# board_0_7v.net
KiCad netlist of a schematic drawn in EAGLE
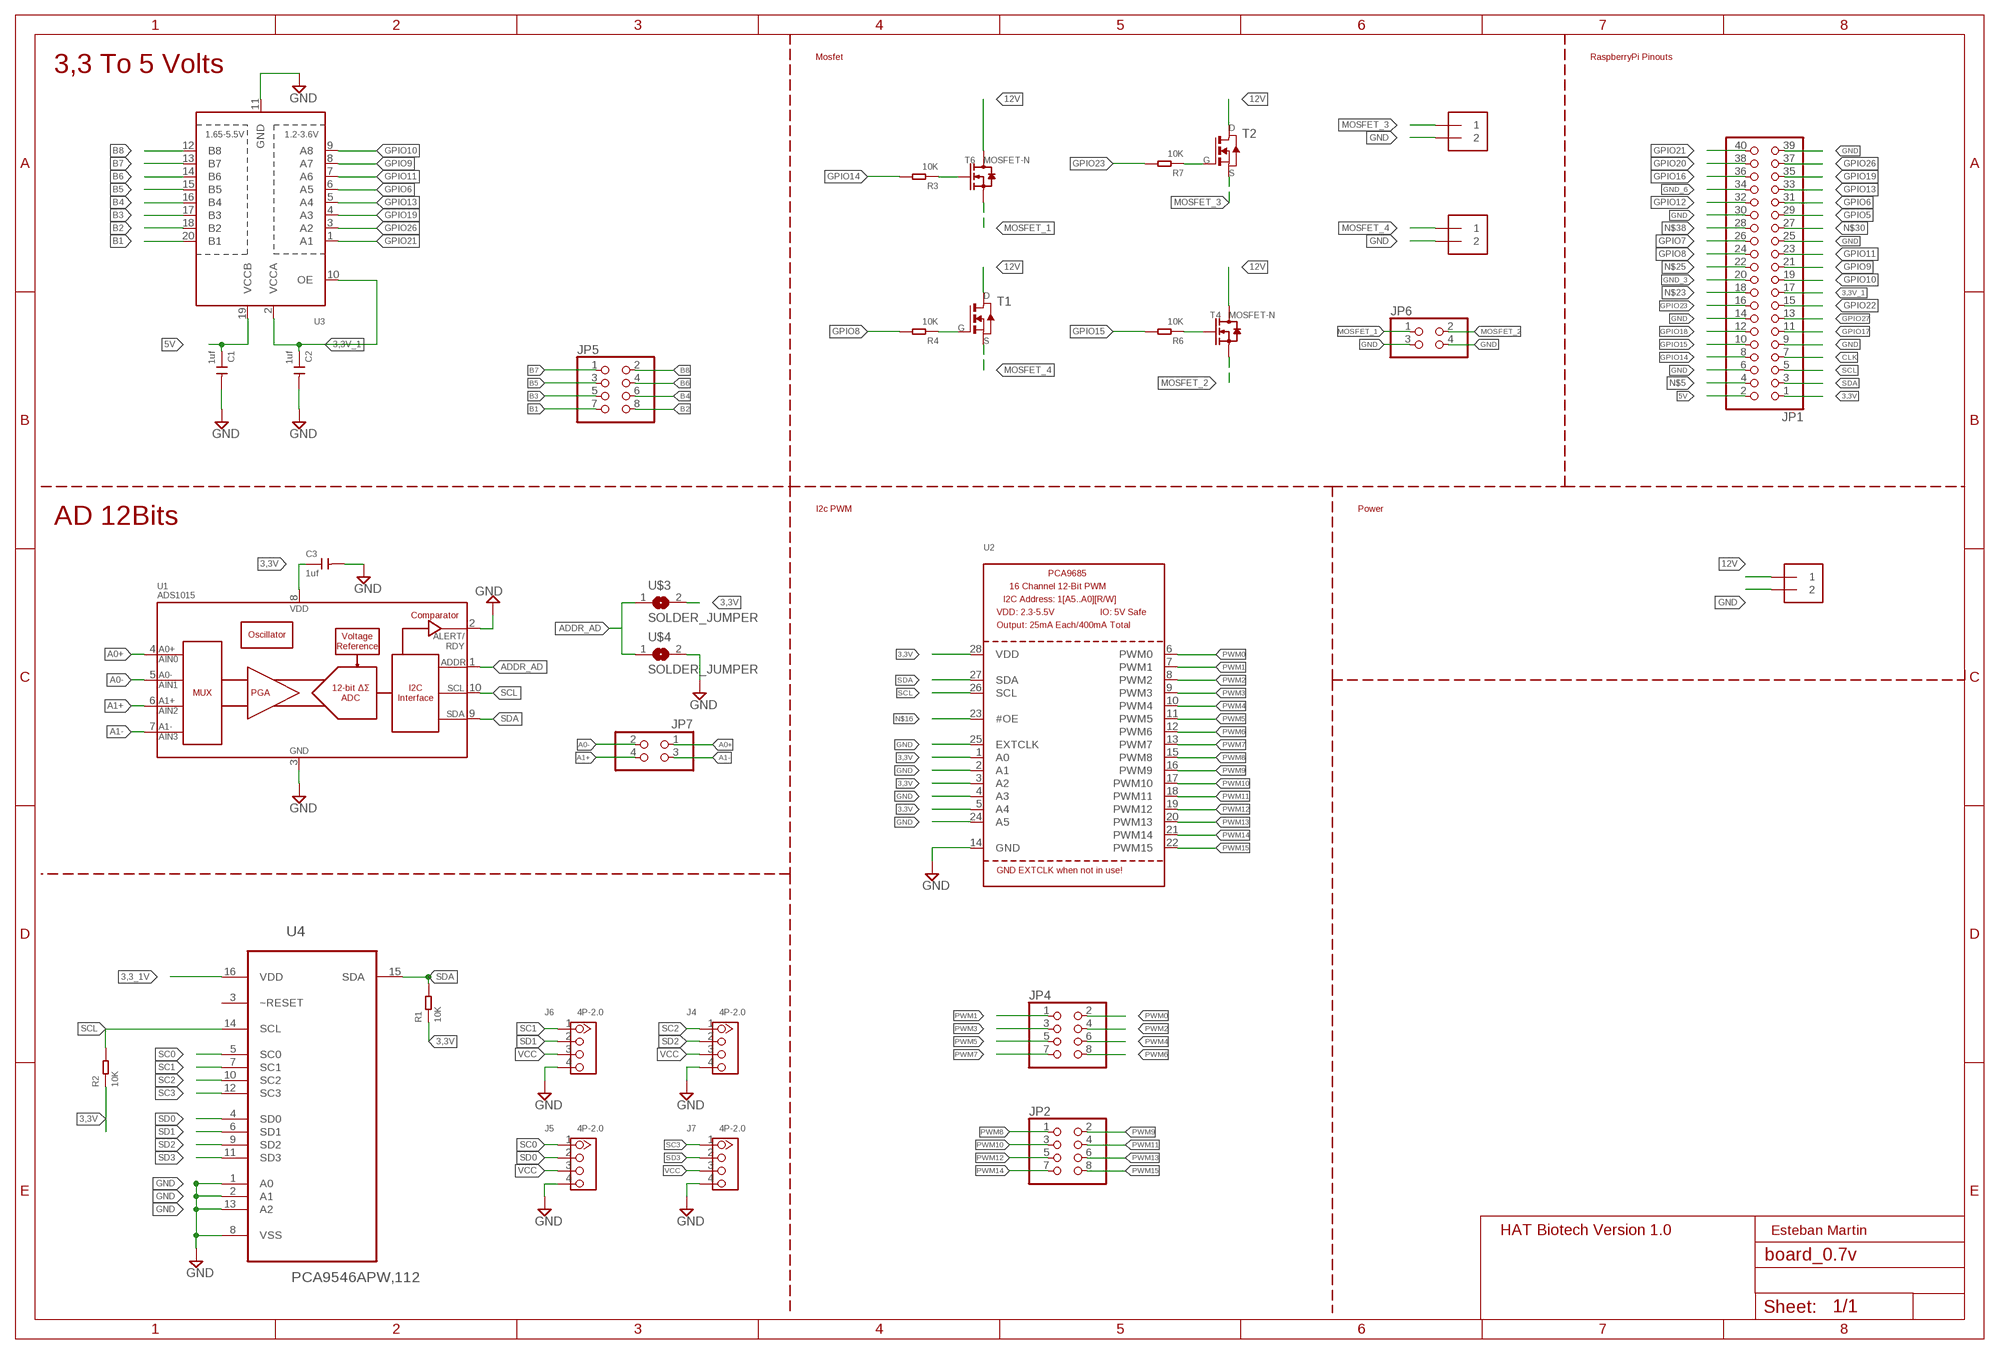
[diagram p0: schematic, sheet 1]

(export (version "E")
  (design (tool "Eeschema 10.0.6"))
  (components
    (comp (ref "C1")
      (value "1uf")
      (footprint "eagle-import:C0805")
      (fields (field (name "MPN") "CC0805KKX7R8BB105"))
      (libsource (lib "eagle-import") (part "CERAMIC-1UF-25V-10%-X7R(0805)"))
    )
    (comp (ref "C2")
      (value "1uf")
      (footprint "eagle-import:C0805")
      (fields (field (name "MPN") "CC0805KKX7R8BB105"))
      (libsource (lib "eagle-import") (part "CERAMIC-1UF-25V-10%-X7R(0805)"))
    )
    (comp (ref "C3")
      (value "1uf")
      (footprint "eagle-import:C0805")
      (fields (field (name "MPN") "CC0805KKX7R8BB105"))
      (libsource (lib "eagle-import") (part "CERAMIC-1UF-25V-10%-X7R(0805)"))
    )
    (comp (ref "J1")
      (value "1X2-3.5MM")
      (footprint "eagle-import:1X2-3.5MM")
      (libsource (lib "eagle-import") (part "1X2-3.5MM"))
    )
    (comp (ref "J2")
      (value "1X2-3.5MM")
      (footprint "eagle-import:1X2-3.5MM")
      (libsource (lib "eagle-import") (part "1X2-3.5MM"))
    )
    (comp (ref "J3")
      (value "1X2-3.5MM")
      (footprint "eagle-import:1X2-3.5MM")
      (libsource (lib "eagle-import") (part "1X2-3.5MM"))
    )
    (comp (ref "J4")
      (value "4P-2.0")
      (footprint "eagle-import:HW4-2.0")
      (libsource (lib "eagle-import") (part "GROVE-CONNECTOR-DIP(4P-2.0)"))
    )
    (comp (ref "J5")
      (value "4P-2.0")
      (footprint "eagle-import:HW4-2.0")
      (libsource (lib "eagle-import") (part "GROVE-CONNECTOR-DIP(4P-2.0)"))
    )
    (comp (ref "J6")
      (value "4P-2.0")
      (footprint "eagle-import:HW4-2.0")
      (libsource (lib "eagle-import") (part "GROVE-CONNECTOR-DIP(4P-2.0)"))
    )
    (comp (ref "J7")
      (value "4P-2.0")
      (footprint "eagle-import:HW4-2.0")
      (libsource (lib "eagle-import") (part "GROVE-CONNECTOR-DIP(4P-2.0)"))
    )
    (comp (ref "JP1")
      (value "PINHD-2X20")
      (footprint "eagle-import:2X20")
      (libsource (lib "eagle-import") (part "PINHD-2X20"))
    )
    (comp (ref "JP2")
      (value "PINHD-2X4")
      (footprint "eagle-import:2X04")
      (libsource (lib "eagle-import") (part "PINHD-2X4"))
    )
    (comp (ref "JP4")
      (value "PINHD-2X4")
      (footprint "eagle-import:2X04")
      (libsource (lib "eagle-import") (part "PINHD-2X4"))
    )
    (comp (ref "JP5")
      (value "PINHD-2X4")
      (footprint "eagle-import:2X04")
      (libsource (lib "eagle-import") (part "PINHD-2X4"))
    )
    (comp (ref "JP6")
      (value "PINHD-2X2")
      (footprint "eagle-import:2X02")
      (libsource (lib "eagle-import") (part "PINHD-2X2"))
    )
    (comp (ref "JP7")
      (value "PINHD-2X2")
      (footprint "eagle-import:2X02")
      (libsource (lib "eagle-import") (part "PINHD-2X2"))
    )
    (comp (ref "R1")
      (value "10K")
      (footprint "eagle-import:R0805")
      (fields (field (name "MPN") "RC0805FR-0710KL"))
      (libsource (lib "eagle-import") (part "SMD-RES-10K-1%-1/8W(0805)"))
    )
    (comp (ref "R2")
      (value "10K")
      (footprint "eagle-import:R0805")
      (fields (field (name "MPN") "RC0805FR-0710KL"))
      (libsource (lib "eagle-import") (part "SMD-RES-10K-1%-1/8W(0805)"))
    )
    (comp (ref "R3")
      (value "10K")
      (footprint "eagle-import:R0805")
      (fields (field (name "MPN") "RC0805FR-0710KL"))
      (libsource (lib "eagle-import") (part "SMD-RES-10K-1%-1/8W(0805)"))
    )
    (comp (ref "R4")
      (value "10K")
      (footprint "eagle-import:R0805")
      (fields (field (name "MPN") "RC0805FR-0710KL"))
      (libsource (lib "eagle-import") (part "SMD-RES-10K-1%-1/8W(0805)"))
    )
    (comp (ref "R6")
      (value "10K")
      (footprint "eagle-import:R0805")
      (fields (field (name "MPN") "RC0805FR-0710KL"))
      (libsource (lib "eagle-import") (part "SMD-RES-10K-1%-1/8W(0805)"))
    )
    (comp (ref "R7")
      (value "10K")
      (footprint "eagle-import:R0805")
      (fields (field (name "MPN") "RC0805FR-0710KL"))
      (libsource (lib "eagle-import") (part "SMD-RES-10K-1%-1/8W(0805)"))
    )
    (comp (ref "T1")
      (value "NMOSFETTO252")
      (footprint "eagle-import:TO252")
      (libsource (lib "eagle-import") (part "NMOSFETTO252"))
    )
    (comp (ref "T2")
      (value "NMOSFETTO252")
      (footprint "eagle-import:TO252")
      (libsource (lib "eagle-import") (part "NMOSFETTO252"))
    )
    (comp (ref "T4")
      (value "MOSFET-N")
      (footprint "eagle-import:SOT-23")
      (libsource (lib "eagle-import") (part "MOSFET-N"))
    )
    (comp (ref "T6")
      (value "MOSFET-N")
      (footprint "eagle-import:SOT-23")
      (libsource (lib "eagle-import") (part "MOSFET-N"))
    )
    (comp (ref "U$3")
      (value "SOLDER_JUMPER")
      (footprint "eagle-import:SJFAB")
      (libsource (lib "eagle-import") (part "SOLDER_JUMPER"))
    )
    (comp (ref "U$4")
      (value "SOLDER_JUMPER")
      (footprint "eagle-import:SJFAB")
      (libsource (lib "eagle-import") (part "SOLDER_JUMPER"))
    )
    (comp (ref "U1")
      (value "ADS1015")
      (footprint "eagle-import:MSOP10")
      (libsource (lib "eagle-import") (part "ADS1015"))
    )
    (comp (ref "U2")
      (value "PCA9685")
      (footprint "eagle-import:TSSOP28")
      (libsource (lib "eagle-import") (part "PCA9685"))
    )
    (comp (ref "U3")
      (value "TXB0108PWR")
      (footprint "eagle-import:TSSOP20")
      (libsource (lib "eagle-import") (part "TXB0108PWR"))
    )
    (comp (ref "U4")
      (value "PCA9546APW,112")
      (footprint "eagle-import:SOP65P640X110-16N")
      (libsource (lib "eagle-import") (part "PCA9546APW,112"))
    )
  )
  (nets
    (net (code "1") (name "3,3V") (class "Default")
      (node (ref "C3") (pin "1") (pinfunction "1_1") (pintype "passive"))
      (node (ref "JP1") (pin "1") (pinfunction "1_1") (pintype "passive"))
      (node (ref "R1") (pin "1") (pinfunction "1_1") (pintype "passive"))
      (node (ref "R2") (pin "1") (pinfunction "1_1") (pintype "passive"))
      (node (ref "U$3") (pin "2") (pinfunction "2_2") (pintype "passive"))
      (node (ref "U1") (pin "8") (pinfunction "VDD_8") (pintype "bidirectional"))
      (node (ref "U2") (pin "1") (pinfunction "A0_1") (pintype "bidirectional"))
      (node (ref "U2") (pin "28") (pinfunction "VDD_28") (pintype "power_in"))
      (node (ref "U2") (pin "3") (pinfunction "A2_3") (pintype "bidirectional"))
      (node (ref "U2") (pin "5") (pinfunction "A4_5") (pintype "bidirectional"))
    )
    (net (code "2") (name "3,3V_1") (class "Default")
      (node (ref "C2") (pin "1") (pinfunction "1_1") (pintype "passive"))
      (node (ref "JP1") (pin "17") (pinfunction "17_17") (pintype "passive"))
      (node (ref "U3") (pin "10") (pinfunction "OE_10") (pintype "bidirectional"))
      (node (ref "U3") (pin "2") (pinfunction "VCCA_2") (pintype "bidirectional"))
    )
    (net (code "3") (name "3,3_1V") (class "Default")
      (node (ref "U4") (pin "16") (pinfunction "VDD_16") (pintype "power_in"))
    )
    (net (code "4") (name "5V") (class "Default")
      (node (ref "C1") (pin "1") (pinfunction "1_1") (pintype "passive"))
      (node (ref "JP1") (pin "2") (pinfunction "2_2") (pintype "passive"))
      (node (ref "U3") (pin "19") (pinfunction "VCCB_19") (pintype "bidirectional"))
    )
    (net (code "5") (name "12V") (class "Default")
      (node (ref "J2") (pin "1") (pinfunction "1_1") (pintype "passive"))
      (node (ref "T1") (pin "3") (pinfunction "D_3") (pintype "passive"))
      (node (ref "T2") (pin "3") (pinfunction "D_3") (pintype "passive"))
      (node (ref "T4") (pin "3") (pinfunction "D_3") (pintype "passive"))
      (node (ref "T6") (pin "3") (pinfunction "D_3") (pintype "passive"))
    )
    (net (code "6") (name "A0+") (class "Default")
      (node (ref "JP7") (pin "1") (pinfunction "1_1") (pintype "passive"))
      (node (ref "U1") (pin "4") (pinfunction "AIN0_4") (pintype "bidirectional"))
    )
    (net (code "7") (name "A0-") (class "Default")
      (node (ref "JP7") (pin "2") (pinfunction "2_2") (pintype "passive"))
      (node (ref "U1") (pin "5") (pinfunction "AIN1_5") (pintype "bidirectional"))
    )
    (net (code "8") (name "A1+") (class "Default")
      (node (ref "JP7") (pin "4") (pinfunction "4_4") (pintype "passive"))
      (node (ref "U1") (pin "6") (pinfunction "AIN2_6") (pintype "bidirectional"))
    )
    (net (code "9") (name "A1-") (class "Default")
      (node (ref "JP7") (pin "3") (pinfunction "3_3") (pintype "passive"))
      (node (ref "U1") (pin "7") (pinfunction "AIN3_7") (pintype "bidirectional"))
    )
    (net (code "10") (name "ADDR_AD") (class "Default")
      (node (ref "U$3") (pin "1") (pinfunction "1_1") (pintype "passive"))
      (node (ref "U$4") (pin "1") (pinfunction "1_1") (pintype "passive"))
      (node (ref "U1") (pin "1") (pinfunction "ADDR_1") (pintype "bidirectional"))
    )
    (net (code "11") (name "B1") (class "Default")
      (node (ref "JP5") (pin "7") (pinfunction "7_7") (pintype "passive"))
      (node (ref "U3") (pin "20") (pinfunction "B1_20") (pintype "bidirectional"))
    )
    (net (code "12") (name "B2") (class "Default")
      (node (ref "JP5") (pin "8") (pinfunction "8_8") (pintype "passive"))
      (node (ref "U3") (pin "18") (pinfunction "B2_18") (pintype "bidirectional"))
    )
    (net (code "13") (name "B3") (class "Default")
      (node (ref "JP5") (pin "5") (pinfunction "5_5") (pintype "passive"))
      (node (ref "U3") (pin "17") (pinfunction "B3_17") (pintype "bidirectional"))
    )
    (net (code "14") (name "B4") (class "Default")
      (node (ref "JP5") (pin "6") (pinfunction "6_6") (pintype "passive"))
      (node (ref "U3") (pin "16") (pinfunction "B4_16") (pintype "bidirectional"))
    )
    (net (code "15") (name "B5") (class "Default")
      (node (ref "JP5") (pin "3") (pinfunction "3_3") (pintype "passive"))
      (node (ref "U3") (pin "15") (pinfunction "B5_15") (pintype "bidirectional"))
    )
    (net (code "16") (name "B6") (class "Default")
      (node (ref "JP5") (pin "4") (pinfunction "4_4") (pintype "passive"))
      (node (ref "U3") (pin "14") (pinfunction "B6_14") (pintype "bidirectional"))
    )
    (net (code "17") (name "B7") (class "Default")
      (node (ref "JP5") (pin "1") (pinfunction "1_1") (pintype "passive"))
      (node (ref "U3") (pin "13") (pinfunction "B7_13") (pintype "bidirectional"))
    )
    (net (code "18") (name "B8") (class "Default")
      (node (ref "JP5") (pin "2") (pinfunction "2_2") (pintype "passive"))
      (node (ref "U3") (pin "12") (pinfunction "B8_12") (pintype "bidirectional"))
    )
    (net (code "19") (name "CLK") (class "Default")
      (node (ref "JP1") (pin "7") (pinfunction "7_7") (pintype "passive"))
    )
    (net (code "20") (name "GND") (class "Default")
      (node (ref "C1") (pin "2") (pinfunction "2_2") (pintype "passive"))
      (node (ref "C2") (pin "2") (pinfunction "2_2") (pintype "passive"))
      (node (ref "C3") (pin "2") (pinfunction "2_2") (pintype "passive"))
      (node (ref "J1") (pin "2") (pinfunction "2_2") (pintype "passive"))
      (node (ref "J2") (pin "2") (pinfunction "2_2") (pintype "passive"))
      (node (ref "J3") (pin "2") (pinfunction "2_2") (pintype "passive"))
      (node (ref "J4") (pin "4") (pinfunction "4_4") (pintype "bidirectional"))
      (node (ref "J5") (pin "4") (pinfunction "4_4") (pintype "bidirectional"))
      (node (ref "J6") (pin "4") (pinfunction "4_4") (pintype "bidirectional"))
      (node (ref "J7") (pin "4") (pinfunction "4_4") (pintype "bidirectional"))
      (node (ref "JP1") (pin "14") (pinfunction "14_14") (pintype "passive"))
      (node (ref "JP1") (pin "25") (pinfunction "25_25") (pintype "passive"))
      (node (ref "JP1") (pin "30") (pinfunction "30_30") (pintype "passive"))
      (node (ref "JP1") (pin "39") (pinfunction "39_39") (pintype "passive"))
      (node (ref "JP1") (pin "6") (pinfunction "6_6") (pintype "passive"))
      (node (ref "JP1") (pin "9") (pinfunction "9_9") (pintype "passive"))
      (node (ref "JP6") (pin "3") (pinfunction "3_3") (pintype "passive"))
      (node (ref "JP6") (pin "4") (pinfunction "4_4") (pintype "passive"))
      (node (ref "U$4") (pin "2") (pinfunction "2_2") (pintype "passive"))
      (node (ref "U1") (pin "2") (pinfunction "ALERT/RDY_2") (pintype "bidirectional"))
      (node (ref "U1") (pin "3") (pinfunction "VSS_3") (pintype "bidirectional"))
      (node (ref "U2") (pin "14") (pinfunction "GND_14") (pintype "power_in"))
      (node (ref "U2") (pin "2") (pinfunction "A1_2") (pintype "bidirectional"))
      (node (ref "U2") (pin "24") (pinfunction "A5_24") (pintype "bidirectional"))
      (node (ref "U2") (pin "25") (pinfunction "EXTCLK_25") (pintype "input"))
      (node (ref "U2") (pin "4") (pinfunction "A3_4") (pintype "bidirectional"))
      (node (ref "U3") (pin "11") (pinfunction "GND_11") (pintype "bidirectional"))
      (node (ref "U4") (pin "1") (pinfunction "A0_1") (pintype "input"))
      (node (ref "U4") (pin "13") (pinfunction "A2_13") (pintype "input"))
      (node (ref "U4") (pin "2") (pinfunction "A1_2") (pintype "input"))
      (node (ref "U4") (pin "8") (pinfunction "VSS_8") (pintype "passive"))
    )
    (net (code "21") (name "GND_3") (class "Default")
      (node (ref "JP1") (pin "20") (pinfunction "20_20") (pintype "passive"))
    )
    (net (code "22") (name "GND_6") (class "Default")
      (node (ref "JP1") (pin "34") (pinfunction "34_34") (pintype "passive"))
    )
    (net (code "23") (name "GPIO5") (class "Default")
      (node (ref "JP1") (pin "29") (pinfunction "29_29") (pintype "passive"))
    )
    (net (code "24") (name "GPIO6") (class "Default")
      (node (ref "JP1") (pin "31") (pinfunction "31_31") (pintype "passive"))
      (node (ref "U3") (pin "6") (pinfunction "A5_6") (pintype "bidirectional"))
    )
    (net (code "25") (name "GPIO7") (class "Default")
      (node (ref "JP1") (pin "26") (pinfunction "26_26") (pintype "passive"))
    )
    (net (code "26") (name "GPIO8") (class "Default")
      (node (ref "JP1") (pin "24") (pinfunction "24_24") (pintype "passive"))
      (node (ref "R4") (pin "2") (pinfunction "2_2") (pintype "passive"))
    )
    (net (code "27") (name "GPIO9") (class "Default")
      (node (ref "JP1") (pin "21") (pinfunction "21_21") (pintype "passive"))
      (node (ref "U3") (pin "8") (pinfunction "A7_8") (pintype "bidirectional"))
    )
    (net (code "28") (name "GPIO10") (class "Default")
      (node (ref "JP1") (pin "19") (pinfunction "19_19") (pintype "passive"))
      (node (ref "U3") (pin "9") (pinfunction "A8_9") (pintype "bidirectional"))
    )
    (net (code "29") (name "GPIO11") (class "Default")
      (node (ref "JP1") (pin "23") (pinfunction "23_23") (pintype "passive"))
      (node (ref "U3") (pin "7") (pinfunction "A6_7") (pintype "bidirectional"))
    )
    (net (code "30") (name "GPIO12") (class "Default")
      (node (ref "JP1") (pin "32") (pinfunction "32_32") (pintype "passive"))
    )
    (net (code "31") (name "GPIO13") (class "Default")
      (node (ref "JP1") (pin "33") (pinfunction "33_33") (pintype "passive"))
      (node (ref "U3") (pin "5") (pinfunction "A4_5") (pintype "bidirectional"))
    )
    (net (code "32") (name "GPIO14") (class "Default")
      (node (ref "JP1") (pin "8") (pinfunction "8_8") (pintype "passive"))
      (node (ref "R3") (pin "2") (pinfunction "2_2") (pintype "passive"))
    )
    (net (code "33") (name "GPIO15") (class "Default")
      (node (ref "JP1") (pin "10") (pinfunction "10_10") (pintype "passive"))
      (node (ref "R6") (pin "2") (pinfunction "2_2") (pintype "passive"))
    )
    (net (code "34") (name "GPIO16") (class "Default")
      (node (ref "JP1") (pin "36") (pinfunction "36_36") (pintype "passive"))
    )
    (net (code "35") (name "GPIO17") (class "Default")
      (node (ref "JP1") (pin "11") (pinfunction "11_11") (pintype "passive"))
    )
    (net (code "36") (name "GPIO18") (class "Default")
      (node (ref "JP1") (pin "12") (pinfunction "12_12") (pintype "passive"))
    )
    (net (code "37") (name "GPIO19") (class "Default")
      (node (ref "JP1") (pin "35") (pinfunction "35_35") (pintype "passive"))
      (node (ref "U3") (pin "4") (pinfunction "A3_4") (pintype "bidirectional"))
    )
    (net (code "38") (name "GPIO20") (class "Default")
      (node (ref "JP1") (pin "38") (pinfunction "38_38") (pintype "passive"))
    )
    (net (code "39") (name "GPIO21") (class "Default")
      (node (ref "JP1") (pin "40") (pinfunction "40_40") (pintype "passive"))
      (node (ref "U3") (pin "1") (pinfunction "A1_1") (pintype "bidirectional"))
    )
    (net (code "40") (name "GPIO22") (class "Default")
      (node (ref "JP1") (pin "15") (pinfunction "15_15") (pintype "passive"))
    )
    (net (code "41") (name "GPIO23") (class "Default")
      (node (ref "JP1") (pin "16") (pinfunction "16_16") (pintype "passive"))
      (node (ref "R7") (pin "2") (pinfunction "2_2") (pintype "passive"))
    )
    (net (code "42") (name "GPIO26") (class "Default")
      (node (ref "JP1") (pin "37") (pinfunction "37_37") (pintype "passive"))
      (node (ref "U3") (pin "3") (pinfunction "A2_3") (pintype "bidirectional"))
    )
    (net (code "43") (name "GPIO27") (class "Default")
      (node (ref "JP1") (pin "13") (pinfunction "13_13") (pintype "passive"))
    )
    (net (code "44") (name "MOSFET_1") (class "Default")
      (node (ref "JP6") (pin "1") (pinfunction "1_1") (pintype "passive"))
      (node (ref "T6") (pin "2") (pinfunction "S_2") (pintype "passive"))
    )
    (net (code "45") (name "MOSFET_2") (class "Default")
      (node (ref "JP6") (pin "2") (pinfunction "2_2") (pintype "passive"))
      (node (ref "T4") (pin "2") (pinfunction "S_2") (pintype "passive"))
    )
    (net (code "46") (name "MOSFET_3") (class "Default")
      (node (ref "J1") (pin "1") (pinfunction "1_1") (pintype "passive"))
      (node (ref "T2") (pin "2") (pinfunction "S_2") (pintype "passive"))
    )
    (net (code "47") (name "MOSFET_4") (class "Default")
      (node (ref "J3") (pin "1") (pinfunction "1_1") (pintype "passive"))
      (node (ref "T1") (pin "2") (pinfunction "S_2") (pintype "passive"))
    )
    (net (code "48") (name "N$5") (class "Default")
      (node (ref "JP1") (pin "4") (pinfunction "4_4") (pintype "passive"))
    )
    (net (code "49") (name "N$16") (class "Default")
      (node (ref "U2") (pin "23") (pinfunction "#OE_23") (pintype "input"))
    )
    (net (code "50") (name "N$23") (class "Default")
      (node (ref "JP1") (pin "18") (pinfunction "18_18") (pintype "passive"))
    )
    (net (code "51") (name "N$25") (class "Default")
      (node (ref "JP1") (pin "22") (pinfunction "22_22") (pintype "passive"))
    )
    (net (code "52") (name "N$30") (class "Default")
      (node (ref "JP1") (pin "27") (pinfunction "27_27") (pintype "passive"))
    )
    (net (code "53") (name "N$38") (class "Default")
      (node (ref "JP1") (pin "28") (pinfunction "28_28") (pintype "passive"))
    )
    (net (code "54") (name "Net-(T1-G)") (class "Default")
      (node (ref "R4") (pin "1") (pinfunction "1_1") (pintype "passive"))
      (node (ref "T1") (pin "1") (pinfunction "G_1") (pintype "passive"))
    )
    (net (code "55") (name "Net-(T2-G)") (class "Default")
      (node (ref "R7") (pin "1") (pinfunction "1_1") (pintype "passive"))
      (node (ref "T2") (pin "1") (pinfunction "G_1") (pintype "passive"))
    )
    (net (code "56") (name "Net-(T4-G)") (class "Default")
      (node (ref "R6") (pin "1") (pinfunction "1_1") (pintype "passive"))
      (node (ref "T4") (pin "1") (pinfunction "G_1") (pintype "passive"))
    )
    (net (code "57") (name "Net-(T6-G)") (class "Default")
      (node (ref "R3") (pin "1") (pinfunction "1_1") (pintype "passive"))
      (node (ref "T6") (pin "1") (pinfunction "G_1") (pintype "passive"))
    )
    (net (code "58") (name "PWM0") (class "Default")
      (node (ref "JP4") (pin "2") (pinfunction "2_2") (pintype "passive"))
      (node (ref "U2") (pin "6") (pinfunction "PWM0_6") (pintype "output"))
    )
    (net (code "59") (name "PWM1") (class "Default")
      (node (ref "JP4") (pin "1") (pinfunction "1_1") (pintype "passive"))
      (node (ref "U2") (pin "7") (pinfunction "PWM1_7") (pintype "output"))
    )
    (net (code "60") (name "PWM2") (class "Default")
      (node (ref "JP4") (pin "4") (pinfunction "4_4") (pintype "passive"))
      (node (ref "U2") (pin "8") (pinfunction "PWM2_8") (pintype "output"))
    )
    (net (code "61") (name "PWM3") (class "Default")
      (node (ref "JP4") (pin "3") (pinfunction "3_3") (pintype "passive"))
      (node (ref "U2") (pin "9") (pinfunction "PWM3_9") (pintype "output"))
    )
    (net (code "62") (name "PWM4") (class "Default")
      (node (ref "JP4") (pin "6") (pinfunction "6_6") (pintype "passive"))
      (node (ref "U2") (pin "10") (pinfunction "PWM4_10") (pintype "output"))
    )
    (net (code "63") (name "PWM5") (class "Default")
      (node (ref "JP4") (pin "5") (pinfunction "5_5") (pintype "passive"))
      (node (ref "U2") (pin "11") (pinfunction "PWM5_11") (pintype "output"))
    )
    (net (code "64") (name "PWM6") (class "Default")
      (node (ref "JP4") (pin "8") (pinfunction "8_8") (pintype "passive"))
      (node (ref "U2") (pin "12") (pinfunction "PWM6_12") (pintype "output"))
    )
    (net (code "65") (name "PWM7") (class "Default")
      (node (ref "JP4") (pin "7") (pinfunction "7_7") (pintype "passive"))
      (node (ref "U2") (pin "13") (pinfunction "PWM7_13") (pintype "output"))
    )
    (net (code "66") (name "PWM8") (class "Default")
      (node (ref "JP2") (pin "1") (pinfunction "1_1") (pintype "passive"))
      (node (ref "U2") (pin "15") (pinfunction "PWM8_15") (pintype "output"))
    )
    (net (code "67") (name "PWM9") (class "Default")
      (node (ref "JP2") (pin "2") (pinfunction "2_2") (pintype "passive"))
      (node (ref "U2") (pin "16") (pinfunction "PWM9_16") (pintype "output"))
    )
    (net (code "68") (name "PWM10") (class "Default")
      (node (ref "JP2") (pin "3") (pinfunction "3_3") (pintype "passive"))
      (node (ref "U2") (pin "17") (pinfunction "PWM10_17") (pintype "output"))
    )
    (net (code "69") (name "PWM11") (class "Default")
      (node (ref "JP2") (pin "4") (pinfunction "4_4") (pintype "passive"))
      (node (ref "U2") (pin "18") (pinfunction "PWM11_18") (pintype "output"))
    )
    (net (code "70") (name "PWM12") (class "Default")
      (node (ref "JP2") (pin "5") (pinfunction "5_5") (pintype "passive"))
      (node (ref "U2") (pin "19") (pinfunction "PWM12_19") (pintype "output"))
    )
    (net (code "71") (name "PWM13") (class "Default")
      (node (ref "JP2") (pin "6") (pinfunction "6_6") (pintype "passive"))
      (node (ref "U2") (pin "20") (pinfunction "PWM13_20") (pintype "output"))
    )
    (net (code "72") (name "PWM14") (class "Default")
      (node (ref "JP2") (pin "7") (pinfunction "7_7") (pintype "passive"))
      (node (ref "U2") (pin "21") (pinfunction "PWM14_21") (pintype "output"))
    )
    (net (code "73") (name "PWM15") (class "Default")
      (node (ref "JP2") (pin "8") (pinfunction "8_8") (pintype "passive"))
      (node (ref "U2") (pin "22") (pinfunction "PWM15_22") (pintype "output"))
    )
    (net (code "74") (name "SC0") (class "Default")
      (node (ref "J5") (pin "1") (pinfunction "1_1") (pintype "bidirectional"))
      (node (ref "U4") (pin "5") (pinfunction "SC0_5") (pintype "input"))
    )
    (net (code "75") (name "SC1") (class "Default")
      (node (ref "J6") (pin "1") (pinfunction "1_1") (pintype "bidirectional"))
      (node (ref "U4") (pin "7") (pinfunction "SC1_7") (pintype "input"))
    )
    (net (code "76") (name "SC2") (class "Default")
      (node (ref "J4") (pin "1") (pinfunction "1_1") (pintype "bidirectional"))
      (node (ref "U4") (pin "10") (pinfunction "SC2_10") (pintype "input"))
    )
    (net (code "77") (name "SC3") (class "Default")
      (node (ref "J7") (pin "1") (pinfunction "1_1") (pintype "bidirectional"))
      (node (ref "U4") (pin "12") (pinfunction "SC3_12") (pintype "input"))
    )
    (net (code "78") (name "SCL") (class "Default")
      (node (ref "JP1") (pin "5") (pinfunction "5_5") (pintype "passive"))
      (node (ref "R2") (pin "2") (pinfunction "2_2") (pintype "passive"))
      (node (ref "U1") (pin "10") (pinfunction "SCL_10") (pintype "bidirectional"))
      (node (ref "U2") (pin "26") (pinfunction "SCL_26") (pintype "bidirectional"))
      (node (ref "U4") (pin "14") (pinfunction "SCL_14") (pintype "bidirectional"))
    )
    (net (code "79") (name "SD0") (class "Default")
      (node (ref "J5") (pin "2") (pinfunction "2_2") (pintype "bidirectional"))
      (node (ref "U4") (pin "4") (pinfunction "SD0_4") (pintype "input"))
    )
    (net (code "80") (name "SD1") (class "Default")
      (node (ref "J6") (pin "2") (pinfunction "2_2") (pintype "bidirectional"))
      (node (ref "U4") (pin "6") (pinfunction "SD1_6") (pintype "input"))
    )
    (net (code "81") (name "SD2") (class "Default")
      (node (ref "J4") (pin "2") (pinfunction "2_2") (pintype "bidirectional"))
      (node (ref "U4") (pin "9") (pinfunction "SD2_9") (pintype "input"))
    )
    (net (code "82") (name "SD3") (class "Default")
      (node (ref "J7") (pin "2") (pinfunction "2_2") (pintype "bidirectional"))
      (node (ref "U4") (pin "11") (pinfunction "SD3_11") (pintype "input"))
    )
    (net (code "83") (name "SDA") (class "Default")
      (node (ref "JP1") (pin "3") (pinfunction "3_3") (pintype "passive"))
      (node (ref "R1") (pin "2") (pinfunction "2_2") (pintype "passive"))
      (node (ref "U1") (pin "9") (pinfunction "SDA_9") (pintype "bidirectional"))
      (node (ref "U2") (pin "27") (pinfunction "SDA_27") (pintype "bidirectional"))
      (node (ref "U4") (pin "15") (pinfunction "SDA_15") (pintype "bidirectional"))
    )
    (net (code "84") (name "VCC") (class "Default")
      (node (ref "J4") (pin "3") (pinfunction "3_3") (pintype "bidirectional"))
      (node (ref "J5") (pin "3") (pinfunction "3_3") (pintype "bidirectional"))
      (node (ref "J6") (pin "3") (pinfunction "3_3") (pintype "bidirectional"))
      (node (ref "J7") (pin "3") (pinfunction "3_3") (pintype "bidirectional"))
    )
    (net (code "85") (name "unconnected-(U4-~{RESET}-Pad3)") (class "Default")
      (node (ref "U4") (pin "3") (pinfunction "~{RESET}_3") (pintype "input"))
    )
  )
)
